# Module_Hub.net
KiCad netlist of a schematic drawn in Altium Designer
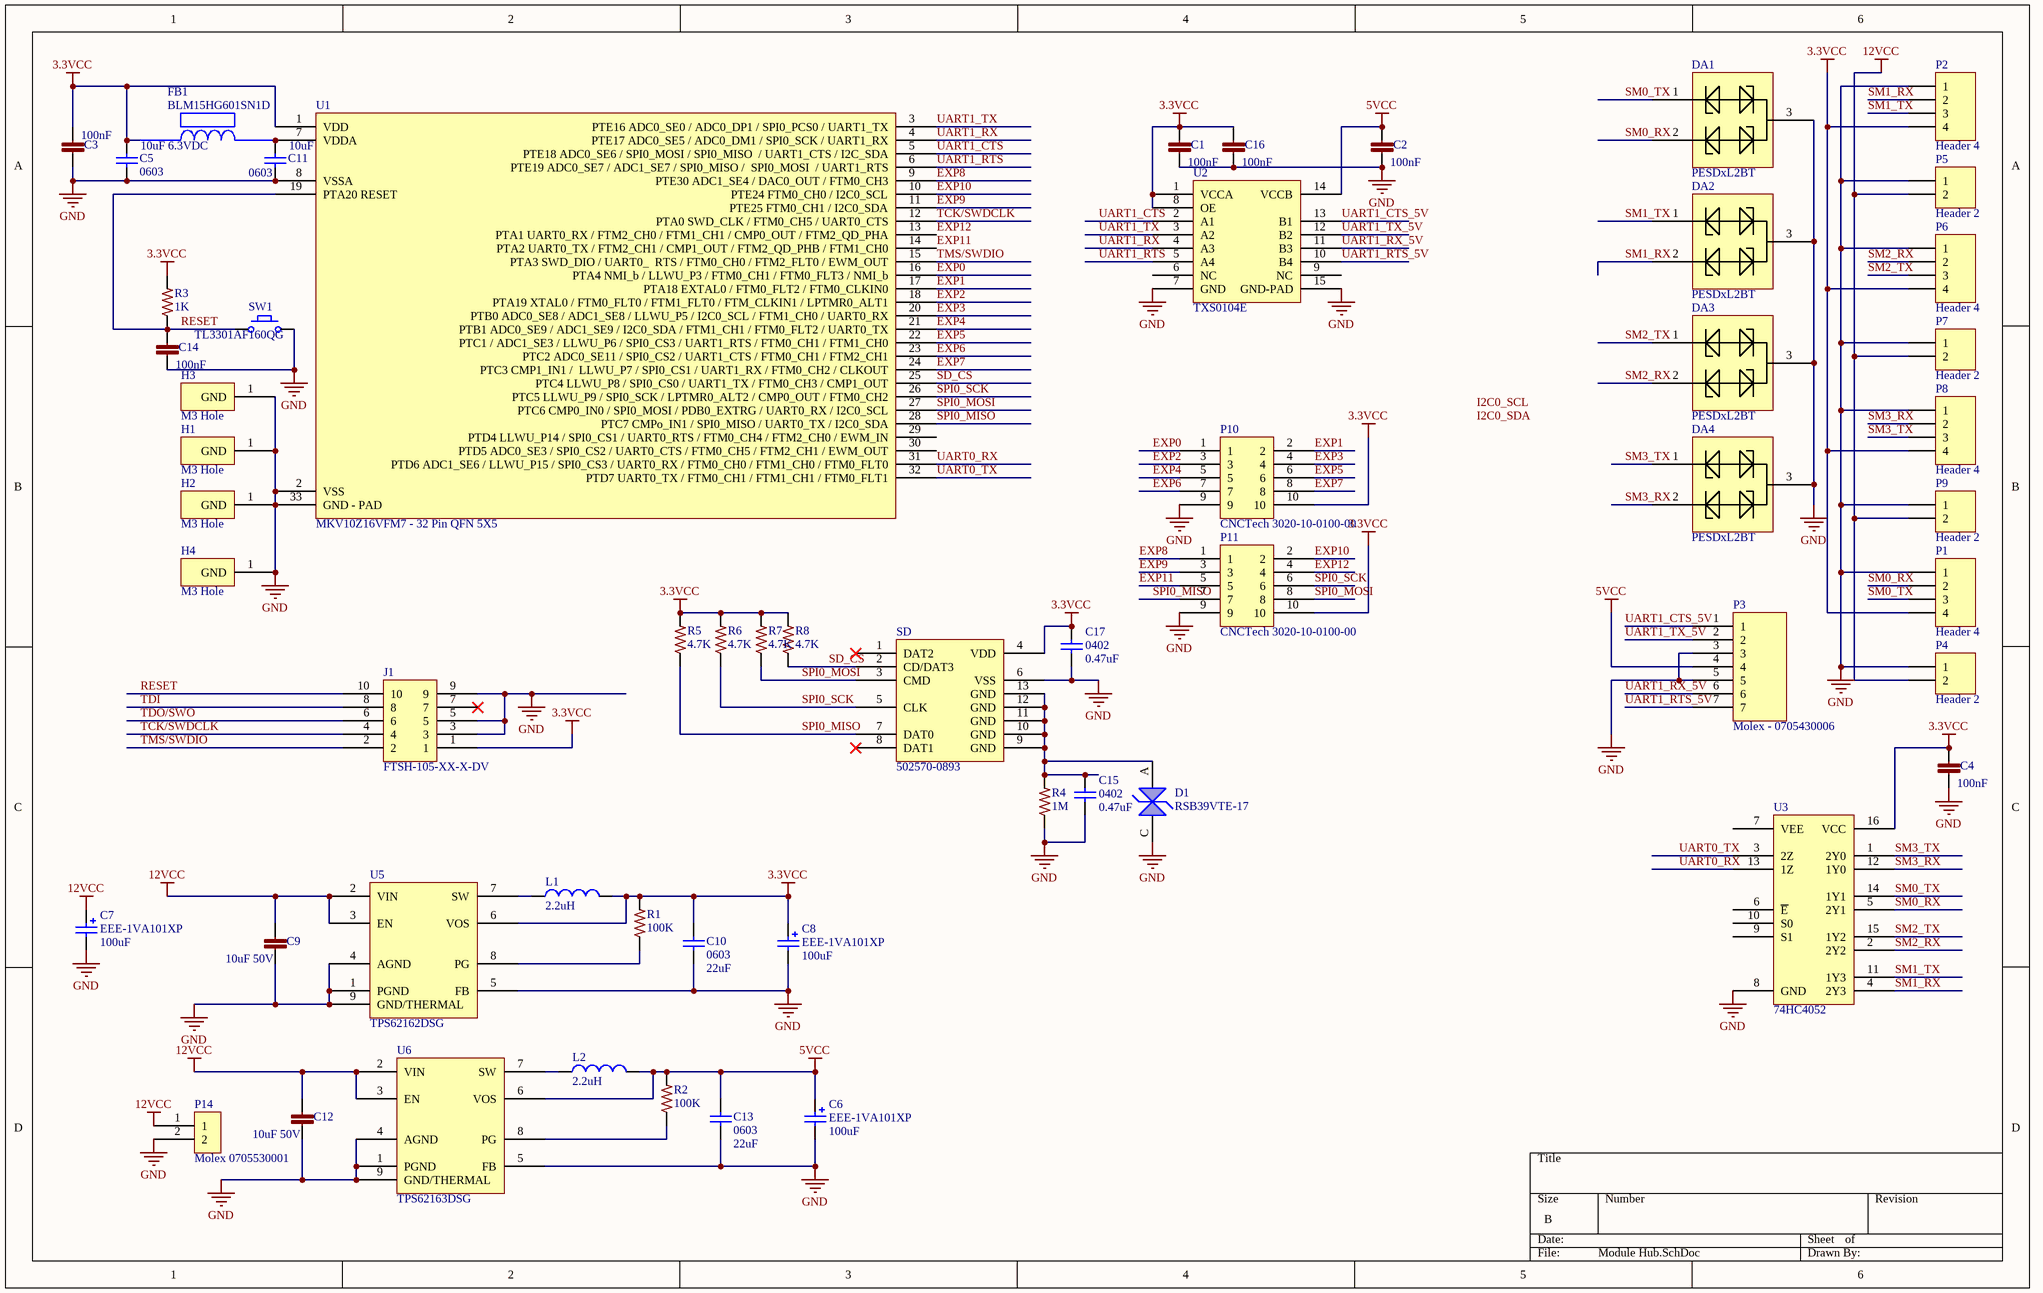
[diagram p0: Module Hub.SchDoc]

(export (version "E")
  (design (tool "Eeschema 10.0.6"))
  (components
    (comp (ref "C1")
      (value "100nF")
      (footprint "C0603")
      (description "CAP CER 0603 100nF 50V 10% X7R")
      (fields
        (field (name "MANUFACTURERPARTNUMBER") "C0603C104K5RACTU")
        (field (name "PUBLISHER") "UltiMachine")
      )
      (libsource (lib "3Delight") (part "C0603C104K5RACTU"))
    )
    (comp (ref "C2")
      (value "100nF")
      (footprint "C0603")
      (description "CAP CER 0603 100nF 50V 10% X7R")
      (fields
        (field (name "MANUFACTURERPARTNUMBER") "C0603C104K5RACTU")
        (field (name "PUBLISHER") "UltiMachine")
      )
      (libsource (lib "3Delight") (part "C0603C104K5RACTU"))
    )
    (comp (ref "C3")
      (value "100nF")
      (footprint "C0603")
      (description "CAP CER 0603 100nF 50V 10% X7R")
      (fields
        (field (name "MANUFACTURERPARTNUMBER") "C0603C104K5RACTU")
        (field (name "PUBLISHER") "UltiMachine")
      )
      (libsource (lib "3Delight") (part "C0603C104K5RACTU"))
    )
    (comp (ref "C4")
      (value "100nF")
      (footprint "C0603")
      (description "CAP CER 0603 100nF 50V 10% X7R")
      (fields
        (field (name "MANUFACTURERPARTNUMBER") "C0603C104K5RACTU")
        (field (name "PUBLISHER") "UltiMachine")
      )
      (libsource (lib "3Delight") (part "C0603C104K5RACTU"))
    )
    (comp (ref "C5")
      (value "0603")
      (footprint "C0603")
      (description "CAP CER 10UF 6.3V 10% JB 0603")
      (fields
        (field (name "MFR PART #") "C1608JB0J106K080AB")
        (field (name "MFR") "TDK")
        (field (name "ALTIUM_VALUE") "10uF 6.3VDC")
      )
      (libsource (lib "Tigershark3D") (part "C1608JB0J106K080AB"))
    )
    (comp (ref "C6")
      (value "EEE-1VA101XP")
      (footprint "EEE-1VA101XP")
      (description "CAP ALUM 100UF 35V 20% SMD")
      (fields (field (name "DIGIKEY PART #") "PCE3951CT-ND") (field (name "ALTIUM_VALUE") "100uF"))
      (libsource (lib "Tigershark3D") (part "EEE-1VA101XP"))
    )
    (comp (ref "C7")
      (value "EEE-1VA101XP")
      (footprint "EEE-1VA101XP")
      (description "CAP ALUM 100UF 35V 20% SMD")
      (fields (field (name "DIGIKEY PART #") "PCE3951CT-ND") (field (name "ALTIUM_VALUE") "100uF"))
      (libsource (lib "Tigershark3D") (part "EEE-1VA101XP"))
    )
    (comp (ref "C8")
      (value "EEE-1VA101XP")
      (footprint "EEE-1VA101XP")
      (description "CAP ALUM 100UF 35V 20% SMD")
      (fields (field (name "DIGIKEY PART #") "PCE3951CT-ND") (field (name "ALTIUM_VALUE") "100uF"))
      (libsource (lib "Tigershark3D") (part "EEE-1VA101XP"))
    )
    (comp (ref "C9")
      (value "10uF 50V")
      (footprint "C1206")
      (description "CAP CER 10UF 50V 10% X5R 1206")
      (fields
        (field (name "MANUFACTURER") "Samsung")
        (field (name "MANUFACTURERPARTNUMBER") "CL31A106KBHNNNE")
        (field (name "PUBLISHER") "UltiMachine")
      )
      (libsource (lib "Tigershark3D") (part "CL31A106KBHNNNE"))
    )
    (comp (ref "C10")
      (value "0603")
      (footprint "C0805")
      (description "CAP CER 22UF 6.3V 10% X5R 0805")
      (fields
        (field (name "MFR PART #") "CL21A226KQQNNNE")
        (field (name "MFR") "Samsung")
        (field (name "ALTIUM_VALUE") "22uF")
      )
      (libsource (lib "Sensor Package") (part "CL21A226KQQNNNE"))
    )
    (comp (ref "C11")
      (value "0603")
      (footprint "C0603")
      (description "CAP CER 10UF 6.3V 10% JB 0603")
      (fields
        (field (name "MFR PART #") "C1608JB0J106K080AB")
        (field (name "MFR") "TDK")
        (field (name "ALTIUM_VALUE") "10uF")
      )
      (libsource (lib "Tigershark3D") (part "C1608JB0J106K080AB"))
    )
    (comp (ref "C12")
      (value "10uF 50V")
      (footprint "C1206")
      (description "CAP CER 10UF 50V 10% X5R 1206")
      (fields
        (field (name "MANUFACTURER") "Samsung")
        (field (name "MANUFACTURERPARTNUMBER") "CL31A106KBHNNNE")
        (field (name "PUBLISHER") "UltiMachine")
      )
      (libsource (lib "Tigershark3D") (part "CL31A106KBHNNNE"))
    )
    (comp (ref "C13")
      (value "0603")
      (footprint "C0805")
      (description "CAP CER 22UF 6.3V 10% X5R 0805")
      (fields
        (field (name "MFR PART #") "CL21A226KQQNNNE")
        (field (name "MFR") "Samsung")
        (field (name "ALTIUM_VALUE") "22uF")
      )
      (libsource (lib "Sensor Package") (part "CL21A226KQQNNNE"))
    )
    (comp (ref "C14")
      (value "100nF")
      (footprint "C0402")
      (description "CAP CER 0402 100nF 16V 10% X7R")
      (fields
        (field (name "MANUFACTURERPARTNUMBER") "GRM155R71C104KA88D")
        (field (name "PUBLISHER") "UltiMachine")
      )
      (libsource (lib "3Delight") (part "GRM155R71C104KA88D"))
    )
    (comp (ref "C15")
      (value "0.47uF")
      (footprint "C0402")
      (description "0.47uF 6.3v C0402 - GRM155R60J474KE19D")
      (fields
        (field (name "MFR PART #") "GRM155R60J474KE19D")
        (field (name "MFR") "Murata")
        (field (name "PACKAGEREFERENCE") "0402")
        (field (name "PUBLISHER") "Ultimachine")
      )
      (libsource (lib "Tigershark3D") (part "GRM155R60J474KE19D"))
    )
    (comp (ref "C16")
      (value "100nF")
      (footprint "C0603")
      (description "CAP CER 0603 100nF 50V 10% X7R")
      (fields
        (field (name "MANUFACTURERPARTNUMBER") "C0603C104K5RACTU")
        (field (name "PUBLISHER") "UltiMachine")
      )
      (libsource (lib "3Delight") (part "C0603C104K5RACTU"))
    )
    (comp (ref "C17")
      (value "0.47uF")
      (footprint "C0402")
      (description "0.47uF 6.3v C0402 - GRM155R60J474KE19D")
      (fields
        (field (name "MFR PART #") "GRM155R60J474KE19D")
        (field (name "MFR") "Murata")
        (field (name "PACKAGEREFERENCE") "0402")
        (field (name "PUBLISHER") "Ultimachine")
      )
      (libsource (lib "Tigershark3D") (part "GRM155R60J474KE19D"))
    )
    (comp (ref "D1")
      (value "RSB39VTE-17")
      (footprint "SOD323-R")
      (description "DIODE TVS")
      (libsource (lib "Tigershark3D") (part "RSB39VTE-17"))
    )
    (comp (ref "DA1")
      (value "PESDxL2BT")
      (footprint "SOT95P230X110-3N")
      (description "PESDxL2BT TVS Diode Array 2x")
      (libsource (lib "ZMBo Schematic Library") (part "PESDxL2BT"))
    )
    (comp (ref "DA2")
      (value "PESDxL2BT")
      (footprint "SOT95P230X110-3N")
      (description "PESDxL2BT TVS Diode Array 2x")
      (libsource (lib "ZMBo Schematic Library") (part "PESDxL2BT"))
    )
    (comp (ref "DA3")
      (value "PESDxL2BT")
      (footprint "SOT95P230X110-3N")
      (description "PESDxL2BT TVS Diode Array 2x")
      (libsource (lib "ZMBo Schematic Library") (part "PESDxL2BT"))
    )
    (comp (ref "DA4")
      (value "PESDxL2BT")
      (footprint "SOT95P230X110-3N")
      (description "PESDxL2BT TVS Diode Array 2x")
      (libsource (lib "ZMBo Schematic Library") (part "PESDxL2BT"))
    )
    (comp (ref "FB1")
      (value "BLM15HG601SN1D")
      (footprint "BLM18PG121SN1D")
      (libsource (lib "AHD Part Library") (part "BLM15HG601SN1D"))
    )
    (comp (ref "H1")
      (value "M3 Hole")
      (footprint "Hole-3mm")
      (description "3mm Hole")
      (libsource (lib "Sensor Package") (part "Hole"))
    )
    (comp (ref "H2")
      (value "M3 Hole")
      (footprint "Hole-3mm")
      (description "3mm Hole")
      (libsource (lib "Sensor Package") (part "Hole"))
    )
    (comp (ref "H3")
      (value "M3 Hole")
      (footprint "Hole-3mm")
      (description "3mm Hole")
      (libsource (lib "Sensor Package") (part "Hole"))
    )
    (comp (ref "H4")
      (value "M3 Hole")
      (footprint "Hole-3mm")
      (description "3mm Hole")
      (libsource (lib "Sensor Package") (part "Hole"))
    )
    (comp (ref "J1")
      (value "FTSH-105-XX-X-DV")
      (footprint "FTSH-105-XX-X-DV")
      (libsource (lib "Adams Altium Library") (part "ARM Cortex JTAG-DEBUG Header"))
    )
    (comp (ref "L1")
      (value "2.2uH")
      (footprint "VLS252012T-2R2M1R3")
      (description "VLS252012T-2R2M1R3")
      (fields (field (name "MFR") "TDK Corporation") (field (name "PUBLISHER") "Adam Vadala-Roth"))
      (libsource (lib "Sensor Package") (part "VLS252012T-2R2M1R3"))
    )
    (comp (ref "L2")
      (value "2.2uH")
      (footprint "VLS252012T-2R2M1R3")
      (description "VLS252012T-2R2M1R3")
      (fields (field (name "MFR") "TDK Corporation") (field (name "PUBLISHER") "Adam Vadala-Roth"))
      (libsource (lib "Sensor Package") (part "VLS252012T-2R2M1R3"))
    )
    (comp (ref "P1")
      (value "Header 4")
      (footprint "HDR1X4")
      (description "Header, 4-Pin")
      (fields (field (name "PUBLISHER") "Altium Limited"))
      (libsource (lib "Miscellaneous Connectors") (part "Header 4"))
    )
    (comp (ref "P2")
      (value "Header 4")
      (footprint "HDR1X4")
      (description "Header, 4-Pin")
      (fields (field (name "PUBLISHER") "Altium Limited"))
      (libsource (lib "Miscellaneous Connectors") (part "Header 4"))
    )
    (comp (ref "P3")
      (value "Molex - 0705430006")
      (footprint "0705530041")
      (description "0705530041")
      (fields (field (name "MFR") "Molex"))
      (libsource (lib "Sensor Package") (part "0705530041"))
    )
    (comp (ref "P4")
      (value "Header 2")
      (footprint "HDR1X2")
      (description "Header, 2-Pin")
      (fields (field (name "PUBLISHER") "Altium Limited"))
      (libsource (lib "Miscellaneous Connectors") (part "Header 2"))
    )
    (comp (ref "P5")
      (value "Header 2")
      (footprint "HDR1X2")
      (description "Header, 2-Pin")
      (fields (field (name "PUBLISHER") "Altium Limited"))
      (libsource (lib "Miscellaneous Connectors") (part "Header 2"))
    )
    (comp (ref "P6")
      (value "Header 4")
      (footprint "HDR1X4")
      (description "Header, 4-Pin")
      (fields (field (name "PUBLISHER") "Altium Limited"))
      (libsource (lib "Miscellaneous Connectors") (part "Header 4"))
    )
    (comp (ref "P7")
      (value "Header 2")
      (footprint "HDR1X2")
      (description "Header, 2-Pin")
      (fields (field (name "PUBLISHER") "Altium Limited"))
      (libsource (lib "Miscellaneous Connectors") (part "Header 2"))
    )
    (comp (ref "P8")
      (value "Header 4")
      (footprint "HDR1X4")
      (description "Header, 4-Pin")
      (fields (field (name "PUBLISHER") "Altium Limited"))
      (libsource (lib "Miscellaneous Connectors") (part "Header 4"))
    )
    (comp (ref "P9")
      (value "Header 2")
      (footprint "HDR1X2")
      (description "Header, 2-Pin")
      (fields (field (name "PUBLISHER") "Altium Limited"))
      (libsource (lib "Miscellaneous Connectors") (part "Header 2"))
    )
    (comp (ref "P10")
      (value "CNCTech 3020-10-0100-00")
      (footprint "3020-10-0100-00")
      (fields
        (field (name "MANUFACTURE PART #") "3020-10-0100-00")
        (field (name "MANUFACTURER") "CNCTech")
        (field (name "DIGIKEY PART #") "1175-1609-ND")
      )
      (libsource (lib "Tigershark3D") (part "3020-10-0100-00"))
    )
    (comp (ref "P11")
      (value "CNCTech 3020-10-0100-00")
      (footprint "3020-10-0100-00")
      (fields
        (field (name "MANUFACTURE PART #") "3020-10-0100-00")
        (field (name "MANUFACTURER") "CNCTech")
        (field (name "DIGIKEY PART #") "1175-1609-ND")
      )
      (libsource (lib "Tigershark3D") (part "3020-10-0100-00"))
    )
    (comp (ref "P14")
      (value "Molex 0705530001")
      (footprint "0705530001")
      (description "Molex 0705530002 Right Angle 2.54mm Shrouded Header")
      (fields (field (name "MFR") "Molex"))
      (libsource (lib "Sensor Package") (part "0705530001"))
    )
    (comp (ref "R1")
      (value "100K")
      (footprint "R0603")
      (description "RES 100K OHM 1/10W 1% 0603 SMD")
      (fields
        (field (name "MANUFACTURERPARTNUMBER") "RC0603FR-07100KL")
        (field (name "PUBLISHER") "UltiMachine")
      )
      (libsource (lib "3Delight") (part "RC0603FR-07100KL"))
    )
    (comp (ref "R2")
      (value "100K")
      (footprint "R0603")
      (description "RES 100K OHM 1/10W 1% 0603 SMD")
      (fields
        (field (name "MANUFACTURERPARTNUMBER") "RC0603FR-07100KL")
        (field (name "PUBLISHER") "UltiMachine")
      )
      (libsource (lib "3Delight") (part "RC0603FR-07100KL"))
    )
    (comp (ref "R3")
      (value "1K")
      (footprint "R0603")
      (description "RES 0603 1K 100mW 1%")
      (fields
        (field (name "MANUFACTURERPARTNUMBER") "ERJ-3EKF1001V")
        (field (name "PUBLISHER") "UltiMachine")
      )
      (libsource (lib "3Delight") (part "ERJ-3EKF1001V"))
    )
    (comp (ref "R4")
      (value "1M")
      (footprint "R0402")
      (description "RES 0402 1M 100mW 5%")
      (fields (field (name "MANUFACTURERPARTNUMBER") "ERJ2GEJ105X") (field (name "PUBLISHER") "UltiMachine"))
      (libsource (lib "Tigershark3D") (part "ERJ2GEJ105X"))
    )
    (comp (ref "R5")
      (value "4.7K")
      (footprint "R0603")
      (description "RES 0603 4.7K 100mW 1%")
      (fields (field (name "MANUFACTURERPARTNUMBER") "ERJ3EKF4701V") (field (name "PUBLISHER") "UltiMachine"))
      (libsource (lib "Tigershark3D") (part "ERJ3EKF4701V"))
    )
    (comp (ref "R6")
      (value "4.7K")
      (footprint "R0603")
      (description "RES 0603 4.7K 100mW 1%")
      (fields (field (name "MANUFACTURERPARTNUMBER") "ERJ3EKF4701V") (field (name "PUBLISHER") "UltiMachine"))
      (libsource (lib "Tigershark3D") (part "ERJ3EKF4701V"))
    )
    (comp (ref "R7")
      (value "4.7K")
      (footprint "R0603")
      (description "RES 0603 4.7K 100mW 1%")
      (fields (field (name "MANUFACTURERPARTNUMBER") "ERJ3EKF4701V") (field (name "PUBLISHER") "UltiMachine"))
      (libsource (lib "Tigershark3D") (part "ERJ3EKF4701V"))
    )
    (comp (ref "R8")
      (value "4.7K")
      (footprint "R0603")
      (description "RES 0603 4.7K 100mW 1%")
      (fields (field (name "MANUFACTURERPARTNUMBER") "ERJ3EKF4701V") (field (name "PUBLISHER") "UltiMachine"))
      (libsource (lib "Tigershark3D") (part "ERJ3EKF4701V"))
    )
    (comp (ref "SD")
      (value "502570-0893")
      (footprint "502570-0893 - Molex SD")
      (description "microSD 502570-0893 Molex Part")
      (libsource (lib "Tigershark3D") (part "502570-0893"))
    )
    (comp (ref "SW1")
      (value "TL3301AF160QG")
      (footprint "TL3301AF160QG")
      (libsource (lib "MongoosMini") (part "TL3301AF160QG"))
    )
    (comp (ref "U1")
      (value "MKV10Z16VFM7 - 32 Pin QFN 5X5")
      (footprint "MKV10Z16VFM7")
      (description "IC MCU ARM Cortex M0+ 16KB 32QFN 75MHZ")
      (fields (field (name "MFR") "FreeScale"))
      (libsource (lib "Sensor Package") (part "MKV10Z16VFM7"))
    )
    (comp (ref "U2")
      (value "TXS0104E")
      (footprint "RGY  (S-PVQFN-N14)")
      (description "TXS0104E - Bidriectional Opendrain/pushpull level shift")
      (fields (field (name "MFR") "Texas Instruments") (field (name "MFR PART #") "TXS0104ERGYR"))
      (libsource (lib "Tigershark3D") (part "TXS0104E"))
    )
    (comp (ref "U3")
      (value "74HC4052")
      (footprint "74HC4052")
      (description "Dual 4-channel analog multiplexer/demultiplexer")
      (fields (field (name "MFR") "NXP"))
      (libsource (lib "Sensor Package") (part "74HC4052"))
    )
    (comp (ref "U5")
      (value "TPS62162DSG")
      (footprint "DSG8-1600X900TP")
      (libsource (lib "Adams Altium Library") (part "TPS62162SOP"))
    )
    (comp (ref "U6")
      (value "TPS62163DSG")
      (footprint "DSG8-1600X900TP")
      (libsource (lib "Adams Altium Library") (part "TPS62162SOP"))
    )
  )
  (nets
    (net (code "1") (name "/EXP0") (class "Default")
      (node (ref "P10") (pin "1") (pinfunction "1_1") (pintype "passive"))
      (node (ref "U1") (pin "16") (pinfunction "PTA4_NMI_b_/_LLWU_P3_/_FTM0_CH1_/_FTM0_FLT3_/_NMI_b_16") (pintype "passive"))
    )
    (net (code "2") (name "/EXP1") (class "Default")
      (node (ref "P10") (pin "2") (pinfunction "2_2") (pintype "passive"))
      (node (ref "U1") (pin "17") (pinfunction "PTA18_EXTAL0_/_FTM0_FLT2_/_FTM0_CLKIN0_17") (pintype "passive"))
    )
    (net (code "3") (name "/EXP2") (class "Default")
      (node (ref "P10") (pin "3") (pinfunction "3_3") (pintype "passive"))
      (node (ref "U1") (pin "18") (pinfunction "PTA19_XTAL0_/_FTM0_FLT0_/_FTM1_FLT0_/_FTM_CLKIN1_/_LPTMR0_ALT1_18") (pintype "passive"))
    )
    (net (code "4") (name "/EXP3") (class "Default")
      (node (ref "P10") (pin "4") (pinfunction "4_4") (pintype "passive"))
      (node (ref "U1") (pin "20") (pinfunction "PTB0_ADC0_SE8_/_ADC1_SE8_/_LLWU_P5_/_I2C0_SCL_/_FTM1_CH0_/_UART0_RX_20") (pintype "passive"))
    )
    (net (code "5") (name "/EXP4") (class "Default")
      (node (ref "P10") (pin "5") (pinfunction "5_5") (pintype "passive"))
      (node (ref "U1") (pin "21") (pinfunction "PTB1_ADC0_SE9_/_ADC1_SE9_/_I2C0_SDA_/_FTM1_CH1_/_FTM0_FLT2_/_UART0_TX_21") (pintype "passive"))
    )
    (net (code "6") (name "/EXP5") (class "Default")
      (node (ref "P10") (pin "6") (pinfunction "6_6") (pintype "passive"))
      (node (ref "U1") (pin "22") (pinfunction "PTC1_/_ADC1_SE3_/_LLWU_P6_/_SPI0_CS3_/_UART1_RTS_/_FTM0_CH1_/_FTM1_CH0_22") (pintype "passive"))
    )
    (net (code "7") (name "/EXP6") (class "Default")
      (node (ref "P10") (pin "7") (pinfunction "7_7") (pintype "passive"))
      (node (ref "U1") (pin "23") (pinfunction "PTC2_ADC0_SE11_/_SPI0_CS2_/_UART1_CTS_/_FTM0_CH1_/_FTM2_CH1_23") (pintype "passive"))
    )
    (net (code "8") (name "/EXP7") (class "Default")
      (node (ref "P10") (pin "8") (pinfunction "8_8") (pintype "passive"))
      (node (ref "U1") (pin "24") (pinfunction "PTC3_CMP1_IN1_/__LLWU_P7_/_SPI0_CS1_/_UART1_RX_/_FTM0_CH2_/_CLKOUT_24") (pintype "passive"))
    )
    (net (code "9") (name "/EXP8") (class "Default")
      (node (ref "P11") (pin "1") (pinfunction "1_1") (pintype "passive"))
      (node (ref "U1") (pin "9") (pinfunction "PTE30_ADC1_SE4_/_DAC0_OUT_/_FTM0_CH3_9") (pintype "passive"))
    )
    (net (code "10") (name "/EXP9") (class "Default")
      (node (ref "P11") (pin "3") (pinfunction "3_3") (pintype "passive"))
      (node (ref "U1") (pin "11") (pinfunction "PTE25_FTM0_CH1_/_I2C0_SDA_11") (pintype "passive"))
    )
    (net (code "11") (name "/EXP10") (class "Default")
      (node (ref "P11") (pin "2") (pinfunction "2_2") (pintype "passive"))
      (node (ref "U1") (pin "10") (pinfunction "PTE24_FTM0_CH0_/_I2C0_SCL_10") (pintype "passive"))
    )
    (net (code "12") (name "/EXP11") (class "Default")
      (node (ref "P11") (pin "5") (pinfunction "5_5") (pintype "passive"))
      (node (ref "U1") (pin "14") (pinfunction "PTA2_UART0_TX_/_FTM2_CH1_/_CMP1_OUT_/_FTM2_QD_PHB_/_FTM1_CH0_14") (pintype "passive"))
    )
    (net (code "13") (name "/EXP12") (class "Default")
      (node (ref "P11") (pin "4") (pinfunction "4_4") (pintype "passive"))
      (node (ref "U1") (pin "13") (pinfunction "PTA1_UART0_RX_/_FTM2_CH0_/_FTM1_CH1_/_CMP0_OUT_/_FTM2_QD_PHA_13") (pintype "passive"))
    )
    (net (code "16") (name "/RESET") (class "Default")
      (node (ref "C14") (pin "1") (pinfunction "1_1") (pintype "passive"))
      (node (ref "J1") (pin "10") (pinfunction "10_10") (pintype "passive"))
      (node (ref "R3") (pin "1") (pinfunction "1_1") (pintype "passive"))
      (node (ref "SW1") (pin "1") (pintype "passive"))
      (node (ref "U1") (pin "19") (pinfunction "PTA20_RESET_19") (pintype "passive"))
    )
    (net (code "17") (name "/SD_CS") (class "Default")
      (node (ref "R8") (pin "1") (pinfunction "1_1") (pintype "passive"))
      (node (ref "SD") (pin "2") (pinfunction "CD/DAT3_2") (pintype "passive"))
      (node (ref "U1") (pin "25") (pinfunction "PTC4_LLWU_P8_/_SPI0_CS0_/_UART1_TX_/_FTM0_CH3_/_CMP1_OUT_25") (pintype "passive"))
    )
    (net (code "18") (name "/SM0_RX") (class "Default")
      (node (ref "DA1") (pin "2") (pinfunction "2_2") (pintype "passive"))
      (node (ref "P1") (pin "2") (pinfunction "2_2") (pintype "passive"))
      (node (ref "U3") (pin "5") (pinfunction "2Y1_5") (pintype "passive"))
    )
    (net (code "19") (name "/SM0_TX") (class "Default")
      (node (ref "DA1") (pin "1") (pinfunction "1_1") (pintype "passive"))
      (node (ref "P1") (pin "3") (pinfunction "3_3") (pintype "passive"))
      (node (ref "U3") (pin "14") (pinfunction "1Y1_14") (pintype "passive"))
    )
    (net (code "20") (name "/SM1_RX") (class "Default")
      (node (ref "DA2") (pin "2") (pinfunction "2_2") (pintype "passive"))
      (node (ref "P2") (pin "2") (pinfunction "2_2") (pintype "passive"))
      (node (ref "U3") (pin "4") (pinfunction "2Y3_4") (pintype "passive"))
    )
    (net (code "21") (name "/SM1_TX") (class "Default")
      (node (ref "DA2") (pin "1") (pinfunction "1_1") (pintype "passive"))
      (node (ref "P2") (pin "3") (pinfunction "3_3") (pintype "passive"))
      (node (ref "U3") (pin "11") (pinfunction "1Y3_11") (pintype "passive"))
    )
    (net (code "22") (name "/SM2_RX") (class "Default")
      (node (ref "DA3") (pin "2") (pinfunction "2_2") (pintype "passive"))
      (node (ref "P6") (pin "2") (pinfunction "2_2") (pintype "passive"))
      (node (ref "U3") (pin "2") (pinfunction "2Y2_2") (pintype "passive"))
    )
    (net (code "23") (name "/SM2_TX") (class "Default")
      (node (ref "DA3") (pin "1") (pinfunction "1_1") (pintype "passive"))
      (node (ref "P6") (pin "3") (pinfunction "3_3") (pintype "passive"))
      (node (ref "U3") (pin "15") (pinfunction "1Y2_15") (pintype "passive"))
    )
    (net (code "24") (name "/SM3_RX") (class "Default")
      (node (ref "DA4") (pin "2") (pinfunction "2_2") (pintype "passive"))
      (node (ref "P8") (pin "2") (pinfunction "2_2") (pintype "passive"))
      (node (ref "U3") (pin "12") (pinfunction "1Y0_12") (pintype "passive"))
    )
    (net (code "25") (name "/SM3_TX") (class "Default")
      (node (ref "DA4") (pin "1") (pinfunction "1_1") (pintype "passive"))
      (node (ref "P8") (pin "3") (pinfunction "3_3") (pintype "passive"))
      (node (ref "U3") (pin "1") (pinfunction "2Y0_1") (pintype "passive"))
    )
    (net (code "26") (name "/SPI0_MISO") (class "Default")
      (node (ref "P11") (pin "7") (pinfunction "7_7") (pintype "passive"))
      (node (ref "R5") (pin "1") (pinfunction "1_1") (pintype "passive"))
      (node (ref "SD") (pin "7") (pinfunction "DAT0_7") (pintype "passive"))
      (node (ref "U1") (pin "28") (pinfunction "PTC7_CMPo_IN1_/_SPI0_MISO_/_UART0_TX_/_I2C0_SDA_28") (pintype "passive"))
    )
    (net (code "27") (name "/SPI0_MOSI") (class "Default")
      (node (ref "P11") (pin "8") (pinfunction "8_8") (pintype "passive"))
      (node (ref "R7") (pin "1") (pinfunction "1_1") (pintype "passive"))
      (node (ref "SD") (pin "3") (pinfunction "CMD_3") (pintype "passive"))
      (node (ref "U1") (pin "27") (pinfunction "PTC6_CMP0_IN0_/_SPI0_MOSI_/_PDB0_EXTRG_/_UART0_RX_/_I2C0_SCL_27") (pintype "passive"))
    )
    (net (code "28") (name "/SPI0_SCK") (class "Default")
      (node (ref "P11") (pin "6") (pinfunction "6_6") (pintype "passive"))
      (node (ref "R6") (pin "1") (pinfunction "1_1") (pintype "passive"))
      (node (ref "SD") (pin "5") (pinfunction "CLK_5") (pintype "passive"))
      (node (ref "U1") (pin "26") (pinfunction "PTC5_LLWU_P9_/_SPI0_SCK_/_LPTMR0_ALT2_/_CMP0_OUT_/_FTM0_CH2_26") (pintype "passive"))
    )
    (net (code "29") (name "/TCK{slash}SWDCLK") (class "Default")
      (node (ref "J1") (pin "4") (pinfunction "4_4") (pintype "passive"))
      (node (ref "U1") (pin "12") (pinfunction "PTA0_SWD_CLK_/_FTM0_CH5_/_UART0_CTS_12") (pintype "passive"))
    )
    (net (code "30") (name "/TDI") (class "Default")
      (node (ref "J1") (pin "8") (pinfunction "8_8") (pintype "passive"))
    )
    (net (code "31") (name "/TDO{slash}SWO") (class "Default")
      (node (ref "J1") (pin "6") (pinfunction "6_6") (pintype "passive"))
    )
    (net (code "32") (name "/TMS{slash}SWDIO") (class "Default")
      (node (ref "J1") (pin "2") (pinfunction "2_2") (pintype "passive"))
      (node (ref "U1") (pin "15") (pinfunction "PTA3_SWD_DIO_/_UART0___RTS_/_FTM0_CH0_/_FTM2_FLT0_/_EWM_OUT_15") (pintype "passive"))
    )
    (net (code "33") (name "/UART0_RX") (class "Default")
      (node (ref "U1") (pin "31") (pinfunction "PTD6_ADC1_SE6_/_LLWU_P15_/_SPI0_CS3_/_UART0_RX_/_FTM0_CH0_/_FTM1_CH0_/_FTM0_FLT0_31") (pintype "passive"))
      (node (ref "U3") (pin "13") (pinfunction "1Z_13") (pintype "passive"))
    )
    (net (code "34") (name "/UART0_TX") (class "Default")
      (node (ref "U1") (pin "32") (pinfunction "PTD7_UART0_TX_/_FTM0_CH1_/_FTM1_CH1_/_FTM0_FLT1_32") (pintype "passive"))
      (node (ref "U3") (pin "3") (pinfunction "2Z_3") (pintype "passive"))
    )
    (net (code "35") (name "/UART1_CTS") (class "Default")
      (node (ref "U1") (pin "5") (pinfunction "PTE18_ADC0_SE6_/_SPI0_MOSI_/_SPI0_MISO__/_UART1_CTS_/_I2C_SDA_5") (pintype "passive"))
      (node (ref "U2") (pin "2") (pinfunction "A1_2") (pintype "passive"))
    )
    (net (code "36") (name "/UART1_CTS_5V") (class "Default")
      (node (ref "P3") (pin "1") (pinfunction "1_1") (pintype "passive"))
      (node (ref "U2") (pin "13") (pinfunction "B1_13") (pintype "passive"))
    )
    (net (code "37") (name "/UART1_RTS") (class "Default")
      (node (ref "U1") (pin "6") (pinfunction "PTE19_ADC0_SE7_/_ADC1_SE7_/_SPI0_MISO_/__SPI0_MOSI__/_UART1_RTS_6") (pintype "passive"))
      (node (ref "U2") (pin "5") (pinfunction "A4_5") (pintype "passive"))
    )
    (net (code "38") (name "/UART1_RTS_5V") (class "Default")
      (node (ref "P3") (pin "7") (pinfunction "7_7") (pintype "passive"))
      (node (ref "U2") (pin "10") (pinfunction "B4_10") (pintype "passive"))
    )
    (net (code "39") (name "/UART1_RX") (class "Default")
      (node (ref "U1") (pin "4") (pinfunction "PTE17_ADC0_SE5_/_ADC0_DM1_/_SPI0_SCK_/_UART1_RX_4") (pintype "passive"))
      (node (ref "U2") (pin "4") (pinfunction "A3_4") (pintype "passive"))
    )
    (net (code "40") (name "/UART1_RX_5V") (class "Default")
      (node (ref "P3") (pin "6") (pinfunction "6_6") (pintype "passive"))
      (node (ref "U2") (pin "11") (pinfunction "B3_11") (pintype "passive"))
    )
    (net (code "41") (name "/UART1_TX") (class "Default")
      (node (ref "U1") (pin "3") (pinfunction "PTE16_ADC0_SE0_/_ADC0_DP1_/_SPI0_PCS0_/_UART1_TX_3") (pintype "passive"))
      (node (ref "U2") (pin "3") (pinfunction "A2_3") (pintype "passive"))
    )
    (net (code "42") (name "/UART1_TX_5V") (class "Default")
      (node (ref "P3") (pin "2") (pinfunction "2_2") (pintype "passive"))
      (node (ref "U2") (pin "12") (pinfunction "B2_12") (pintype "passive"))
    )
    (net (code "43") (name "3.3VCC") (class "Default")
      (node (ref "C1") (pin "1") (pinfunction "1_1") (pintype "passive"))
      (node (ref "C10") (pin "2") (pinfunction "2_2") (pintype "passive"))
      (node (ref "C16") (pin "1") (pinfunction "1_1") (pintype "passive"))
      (node (ref "C17") (pin "2") (pinfunction "2_2") (pintype "passive"))
      (node (ref "C3") (pin "1") (pinfunction "1_1") (pintype "passive"))
      (node (ref "C4") (pin "1") (pinfunction "1_1") (pintype "passive"))
      (node (ref "C5") (pin "2") (pinfunction "2_2") (pintype "passive"))
      (node (ref "C8") (pin "1") (pinfunction "1_1") (pintype "passive"))
      (node (ref "FB1") (pin "1") (pinfunction "1_1") (pintype "passive"))
      (node (ref "J1") (pin "1") (pinfunction "1_1") (pintype "passive"))
      (node (ref "L1") (pin "2") (pinfunction "2_2") (pintype "passive"))
      (node (ref "P1") (pin "4") (pinfunction "4_4") (pintype "passive"))
      (node (ref "P10") (pin "10") (pinfunction "10_10") (pintype "passive"))
      (node (ref "P11") (pin "10") (pinfunction "10_10") (pintype "passive"))
      (node (ref "P2") (pin "4") (pinfunction "4_4") (pintype "passive"))
      (node (ref "P6") (pin "4") (pinfunction "4_4") (pintype "passive"))
      (node (ref "P8") (pin "4") (pinfunction "4_4") (pintype "passive"))
      (node (ref "R1") (pin "2") (pinfunction "2_2") (pintype "passive"))
      (node (ref "R3") (pin "2") (pinfunction "2_2") (pintype "passive"))
      (node (ref "R5") (pin "2") (pinfunction "2_2") (pintype "passive"))
      (node (ref "R6") (pin "2") (pinfunction "2_2") (pintype "passive"))
      (node (ref "R7") (pin "2") (pinfunction "2_2") (pintype "passive"))
      (node (ref "R8") (pin "2") (pinfunction "2_2") (pintype "passive"))
      (node (ref "SD") (pin "4") (pinfunction "VDD_4") (pintype "passive"))
      (node (ref "U1") (pin "1") (pinfunction "VDD_1") (pintype "passive"))
      (node (ref "U2") (pin "1") (pinfunction "VCCA_1") (pintype "passive"))
      (node (ref "U2") (pin "8") (pinfunction "OE_8") (pintype "passive"))
      (node (ref "U3") (pin "16") (pinfunction "VCC_16") (pintype "passive"))
      (node (ref "U5") (pin "6") (pinfunction "VOS_6") (pintype "passive"))
    )
    (net (code "44") (name "5VCC") (class "Default")
      (node (ref "C13") (pin "2") (pinfunction "2_2") (pintype "passive"))
      (node (ref "C2") (pin "1") (pinfunction "1_1") (pintype "passive"))
      (node (ref "C6") (pin "1") (pinfunction "1_1") (pintype "passive"))
      (node (ref "L2") (pin "2") (pinfunction "2_2") (pintype "passive"))
      (node (ref "P3") (pin "4") (pinfunction "4_4") (pintype "passive"))
      (node (ref "R2") (pin "2") (pinfunction "2_2") (pintype "passive"))
      (node (ref "U2") (pin "14") (pinfunction "VCCB_14") (pintype "passive"))
      (node (ref "U6") (pin "6") (pinfunction "VOS_6") (pintype "passive"))
    )
    (net (code "45") (name "12VCC") (class "Default")
      (node (ref "C12") (pin "1") (pinfunction "1_1") (pintype "passive"))
      (node (ref "C7") (pin "1") (pinfunction "1_1") (pintype "passive"))
      (node (ref "C9") (pin "1") (pinfunction "1_1") (pintype "passive"))
      (node (ref "P14") (pin "1") (pinfunction "1_1") (pintype "passive"))
      (node (ref "P4") (pin "2") (pinfunction "2_2") (pintype "passive"))
      (node (ref "P5") (pin "2") (pinfunction "2_2") (pintype "passive"))
      (node (ref "P7") (pin "2") (pinfunction "2_2") (pintype "passive"))
      (node (ref "P9") (pin "2") (pinfunction "2_2") (pintype "passive"))
      (node (ref "U5") (pin "2") (pinfunction "VIN_2") (pintype "passive"))
      (node (ref "U5") (pin "3") (pinfunction "EN_3") (pintype "passive"))
      (node (ref "U6") (pin "2") (pinfunction "VIN_2") (pintype "passive"))
      (node (ref "U6") (pin "3") (pinfunction "EN_3") (pintype "passive"))
    )
    (net (code "46") (name "GND") (class "Default")
      (node (ref "C1") (pin "2") (pinfunction "2_2") (pintype "passive"))
      (node (ref "C10") (pin "1") (pinfunction "1_1") (pintype "passive"))
      (node (ref "C11") (pin "1") (pinfunction "1_1") (pintype "passive"))
      (node (ref "C12") (pin "2") (pinfunction "2_2") (pintype "passive"))
      (node (ref "C13") (pin "1") (pinfunction "1_1") (pintype "passive"))
      (node (ref "C14") (pin "2") (pinfunction "2_2") (pintype "passive"))
      (node (ref "C15") (pin "1") (pinfunction "1_1") (pintype "passive"))
      (node (ref "C16") (pin "2") (pinfunction "2_2") (pintype "passive"))
      (node (ref "C17") (pin "1") (pinfunction "1_1") (pintype "passive"))
      (node (ref "C2") (pin "2") (pinfunction "2_2") (pintype "passive"))
      (node (ref "C3") (pin "2") (pinfunction "2_2") (pintype "passive"))
      (node (ref "C4") (pin "2") (pinfunction "2_2") (pintype "passive"))
      (node (ref "C5") (pin "1") (pinfunction "1_1") (pintype "passive"))
      (node (ref "C6") (pin "2") (pinfunction "2_2") (pintype "passive"))
      (node (ref "C7") (pin "2") (pinfunction "2_2") (pintype "passive"))
      (node (ref "C8") (pin "2") (pinfunction "2_2") (pintype "passive"))
      (node (ref "C9") (pin "2") (pinfunction "2_2") (pintype "passive"))
      (node (ref "D1") (pin "C") (pinfunction "C_C") (pintype "power_in"))
      (node (ref "DA1") (pin "3") (pinfunction "3_3") (pintype "passive"))
      (node (ref "DA2") (pin "3") (pinfunction "3_3") (pintype "passive"))
      (node (ref "DA3") (pin "3") (pinfunction "3_3") (pintype "passive"))
      (node (ref "DA4") (pin "3") (pinfunction "3_3") (pintype "passive"))
      (node (ref "H1") (pin "1") (pinfunction "GND_1") (pintype "passive"))
      (node (ref "H2") (pin "1") (pinfunction "GND_1") (pintype "passive"))
      (node (ref "H3") (pin "1") (pinfunction "GND_1") (pintype "passive"))
      (node (ref "H4") (pin "1") (pinfunction "GND_1") (pintype "passive"))
      (node (ref "J1") (pin "3") (pinfunction "3_3") (pintype "passive"))
      (node (ref "J1") (pin "5") (pinfunction "5_5") (pintype "passive"))
      (node (ref "J1") (pin "9") (pinfunction "9_9") (pintype "passive"))
      (node (ref "P1") (pin "1") (pinfunction "1_1") (pintype "passive"))
      (node (ref "P10") (pin "9") (pinfunction "9_9") (pintype "passive"))
      (node (ref "P11") (pin "9") (pinfunction "9_9") (pintype "passive"))
      (node (ref "P14") (pin "2") (pinfunction "2_2") (pintype "passive"))
      (node (ref "P2") (pin "1") (pinfunction "1_1") (pintype "passive"))
      (node (ref "P3") (pin "3") (pinfunction "3_3") (pintype "passive"))
      (node (ref "P3") (pin "5") (pinfunction "5_5") (pintype "passive"))
      (node (ref "P4") (pin "1") (pinfunction "1_1") (pintype "passive"))
      (node (ref "P5") (pin "1") (pinfunction "1_1") (pintype "passive"))
      (node (ref "P6") (pin "1") (pinfunction "1_1") (pintype "passive"))
      (node (ref "P7") (pin "1") (pinfunction "1_1") (pintype "passive"))
      (node (ref "P8") (pin "1") (pinfunction "1_1") (pintype "passive"))
      (node (ref "P9") (pin "1") (pinfunction "1_1") (pintype "passive"))
      (node (ref "R4") (pin "1") (pinfunction "1_1") (pintype "passive"))
      (node (ref "SD") (pin "6") (pinfunction "VSS_6") (pintype "passive"))
      (node (ref "SW1") (pin "2") (pintype "passive"))
      (node (ref "U1") (pin "2") (pinfunction "VSS_2") (pintype "passive"))
      (node (ref "U1") (pin "33") (pinfunction "GND_-_PAD_33") (pintype "passive"))
      (node (ref "U1") (pin "8") (pinfunction "VSSA_8") (pintype "passive"))
      (node (ref "U2") (pin "15") (pinfunction "GND-PAD_15") (pintype "passive"))
      (node (ref "U2") (pin "7") (pinfunction "GND_7") (pintype "passive"))
      (node (ref "U3") (pin "8") (pinfunction "GND_8") (pintype "passive"))
      (node (ref "U5") (pin "1") (pinfunction "PGND_1") (pintype "passive"))
      (node (ref "U5") (pin "4") (pinfunction "AGND_4") (pintype "passive"))
      (node (ref "U5") (pin "5") (pinfunction "FB_5") (pintype "passive"))
      (node (ref "U5") (pin "9") (pinfunction "GND/THERMAL_9") (pintype "passive"))
      (node (ref "U6") (pin "1") (pinfunction "PGND_1") (pintype "passive"))
      (node (ref "U6") (pin "4") (pinfunction "AGND_4") (pintype "passive"))
      (node (ref "U6") (pin "5") (pinfunction "FB_5") (pintype "passive"))
      (node (ref "U6") (pin "9") (pinfunction "GND/THERMAL_9") (pintype "passive"))
    )
    (net (code "47") (name "Net-(C15-Pad2)") (class "Default")
      (node (ref "C15") (pin "2") (pinfunction "2_2") (pintype "passive"))
      (node (ref "D1") (pin "A") (pinfunction "A_A") (pintype "power_in"))
      (node (ref "R4") (pin "2") (pinfunction "2_2") (pintype "passive"))
      (node (ref "SD") (pin "10") (pinfunction "GND_10") (pintype "passive"))
      (node (ref "SD") (pin "11") (pinfunction "GND_11") (pintype "passive"))
      (node (ref "SD") (pin "12") (pinfunction "GND_12") (pintype "passive"))
      (node (ref "SD") (pin "13") (pinfunction "GND_13") (pintype "passive"))
      (node (ref "SD") (pin "9") (pinfunction "GND_9") (pintype "passive"))
    )
    (net (code "48") (name "Net-(U1-VDDA)") (class "Default")
      (node (ref "C11") (pin "2") (pinfunction "2_2") (pintype "passive"))
      (node (ref "FB1") (pin "2") (pinfunction "2_2") (pintype "passive"))
      (node (ref "U1") (pin "7") (pinfunction "VDDA_7") (pintype "passive"))
    )
    (net (code "49") (name "Net-(U5-PG)") (class "Default")
      (node (ref "R1") (pin "1") (pinfunction "1_1") (pintype "passive"))
      (node (ref "U5") (pin "8") (pinfunction "PG_8") (pintype "passive"))
    )
    (net (code "50") (name "Net-(U5-SW)") (class "Default")
      (node (ref "L1") (pin "1") (pinfunction "1_1") (pintype "passive"))
      (node (ref "U5") (pin "7") (pinfunction "SW_7") (pintype "passive"))
    )
    (net (code "51") (name "Net-(U6-PG)") (class "Default")
      (node (ref "R2") (pin "1") (pinfunction "1_1") (pintype "passive"))
      (node (ref "U6") (pin "8") (pinfunction "PG_8") (pintype "passive"))
    )
    (net (code "52") (name "Net-(U6-SW)") (class "Default")
      (node (ref "L2") (pin "1") (pinfunction "1_1") (pintype "passive"))
      (node (ref "U6") (pin "7") (pinfunction "SW_7") (pintype "passive"))
    )
    (net (code "53") (name "unconnected-(J1-Pad7)") (class "Default")
      (node (ref "J1") (pin "7") (pinfunction "7_7") (pintype "passive+no_connect"))
    )
    (net (code "54") (name "unconnected-(SD-DAT1-Pad8)") (class "Default")
      (node (ref "SD") (pin "8") (pinfunction "DAT1_8") (pintype "passive+no_connect"))
    )
    (net (code "55") (name "unconnected-(SD-DAT2-Pad1)") (class "Default")
      (node (ref "SD") (pin "1") (pinfunction "DAT2_1") (pintype "passive+no_connect"))
    )
    (net (code "56") (name "unconnected-(U1-PTD4_LLWU_P14_{slash}_SPI0_CS1_{slash}_UART0_RTS_{slash}_FTM0_CH4_{slash}_FTM2_CH0_{slash}_EWM_IN-Pad29)") (class "Default")
      (node (ref "U1") (pin "29") (pinfunction "PTD4_LLWU_P14_/_SPI0_CS1_/_UART0_RTS_/_FTM0_CH4_/_FTM2_CH0_/_EWM_IN_29") (pintype "passive"))
    )
    (net (code "57") (name "unconnected-(U1-PTD5_ADC0_SE3_{slash}_SPI0_CS2_{slash}_UART0_CTS_{slash}_FTM0_CH5_{slash}_FTM2_CH1_{slash}_EWM_OUT-Pad30)") (class "Default")
      (node (ref "U1") (pin "30") (pinfunction "PTD5_ADC0_SE3_/_SPI0_CS2_/_UART0_CTS_/_FTM0_CH5_/_FTM2_CH1_/_EWM_OUT_30") (pintype "passive"))
    )
    (net (code "58") (name "unconnected-(U2-NC-Pad6)") (class "Default")
      (node (ref "U2") (pin "6") (pinfunction "NC_6") (pintype "passive"))
    )
    (net (code "59") (name "unconnected-(U2-NC-Pad9)") (class "Default")
      (node (ref "U2") (pin "9") (pinfunction "NC_9") (pintype "passive"))
    )
    (net (code "60") (name "unconnected-(U3-S0-Pad10)") (class "Default")
      (node (ref "U3") (pin "10") (pinfunction "S0_10") (pintype "passive"))
    )
    (net (code "61") (name "unconnected-(U3-S1-Pad9)") (class "Default")
      (node (ref "U3") (pin "9") (pinfunction "S1_9") (pintype "passive"))
    )
    (net (code "62") (name "unconnected-(U3-VEE-Pad7)") (class "Default")
      (node (ref "U3") (pin "7") (pinfunction "VEE_7") (pintype "passive"))
    )
    (net (code "63") (name "unconnected-(U3-~{E}-Pad6)") (class "Default")
      (node (ref "U3") (pin "6") (pinfunction "~{E}_6") (pintype "passive"))
    )
  )
)
